# SCH_CarAccessoryKitNoBatteryV1_0.net
KiCad netlist of a schematic drawn in EasyEDA
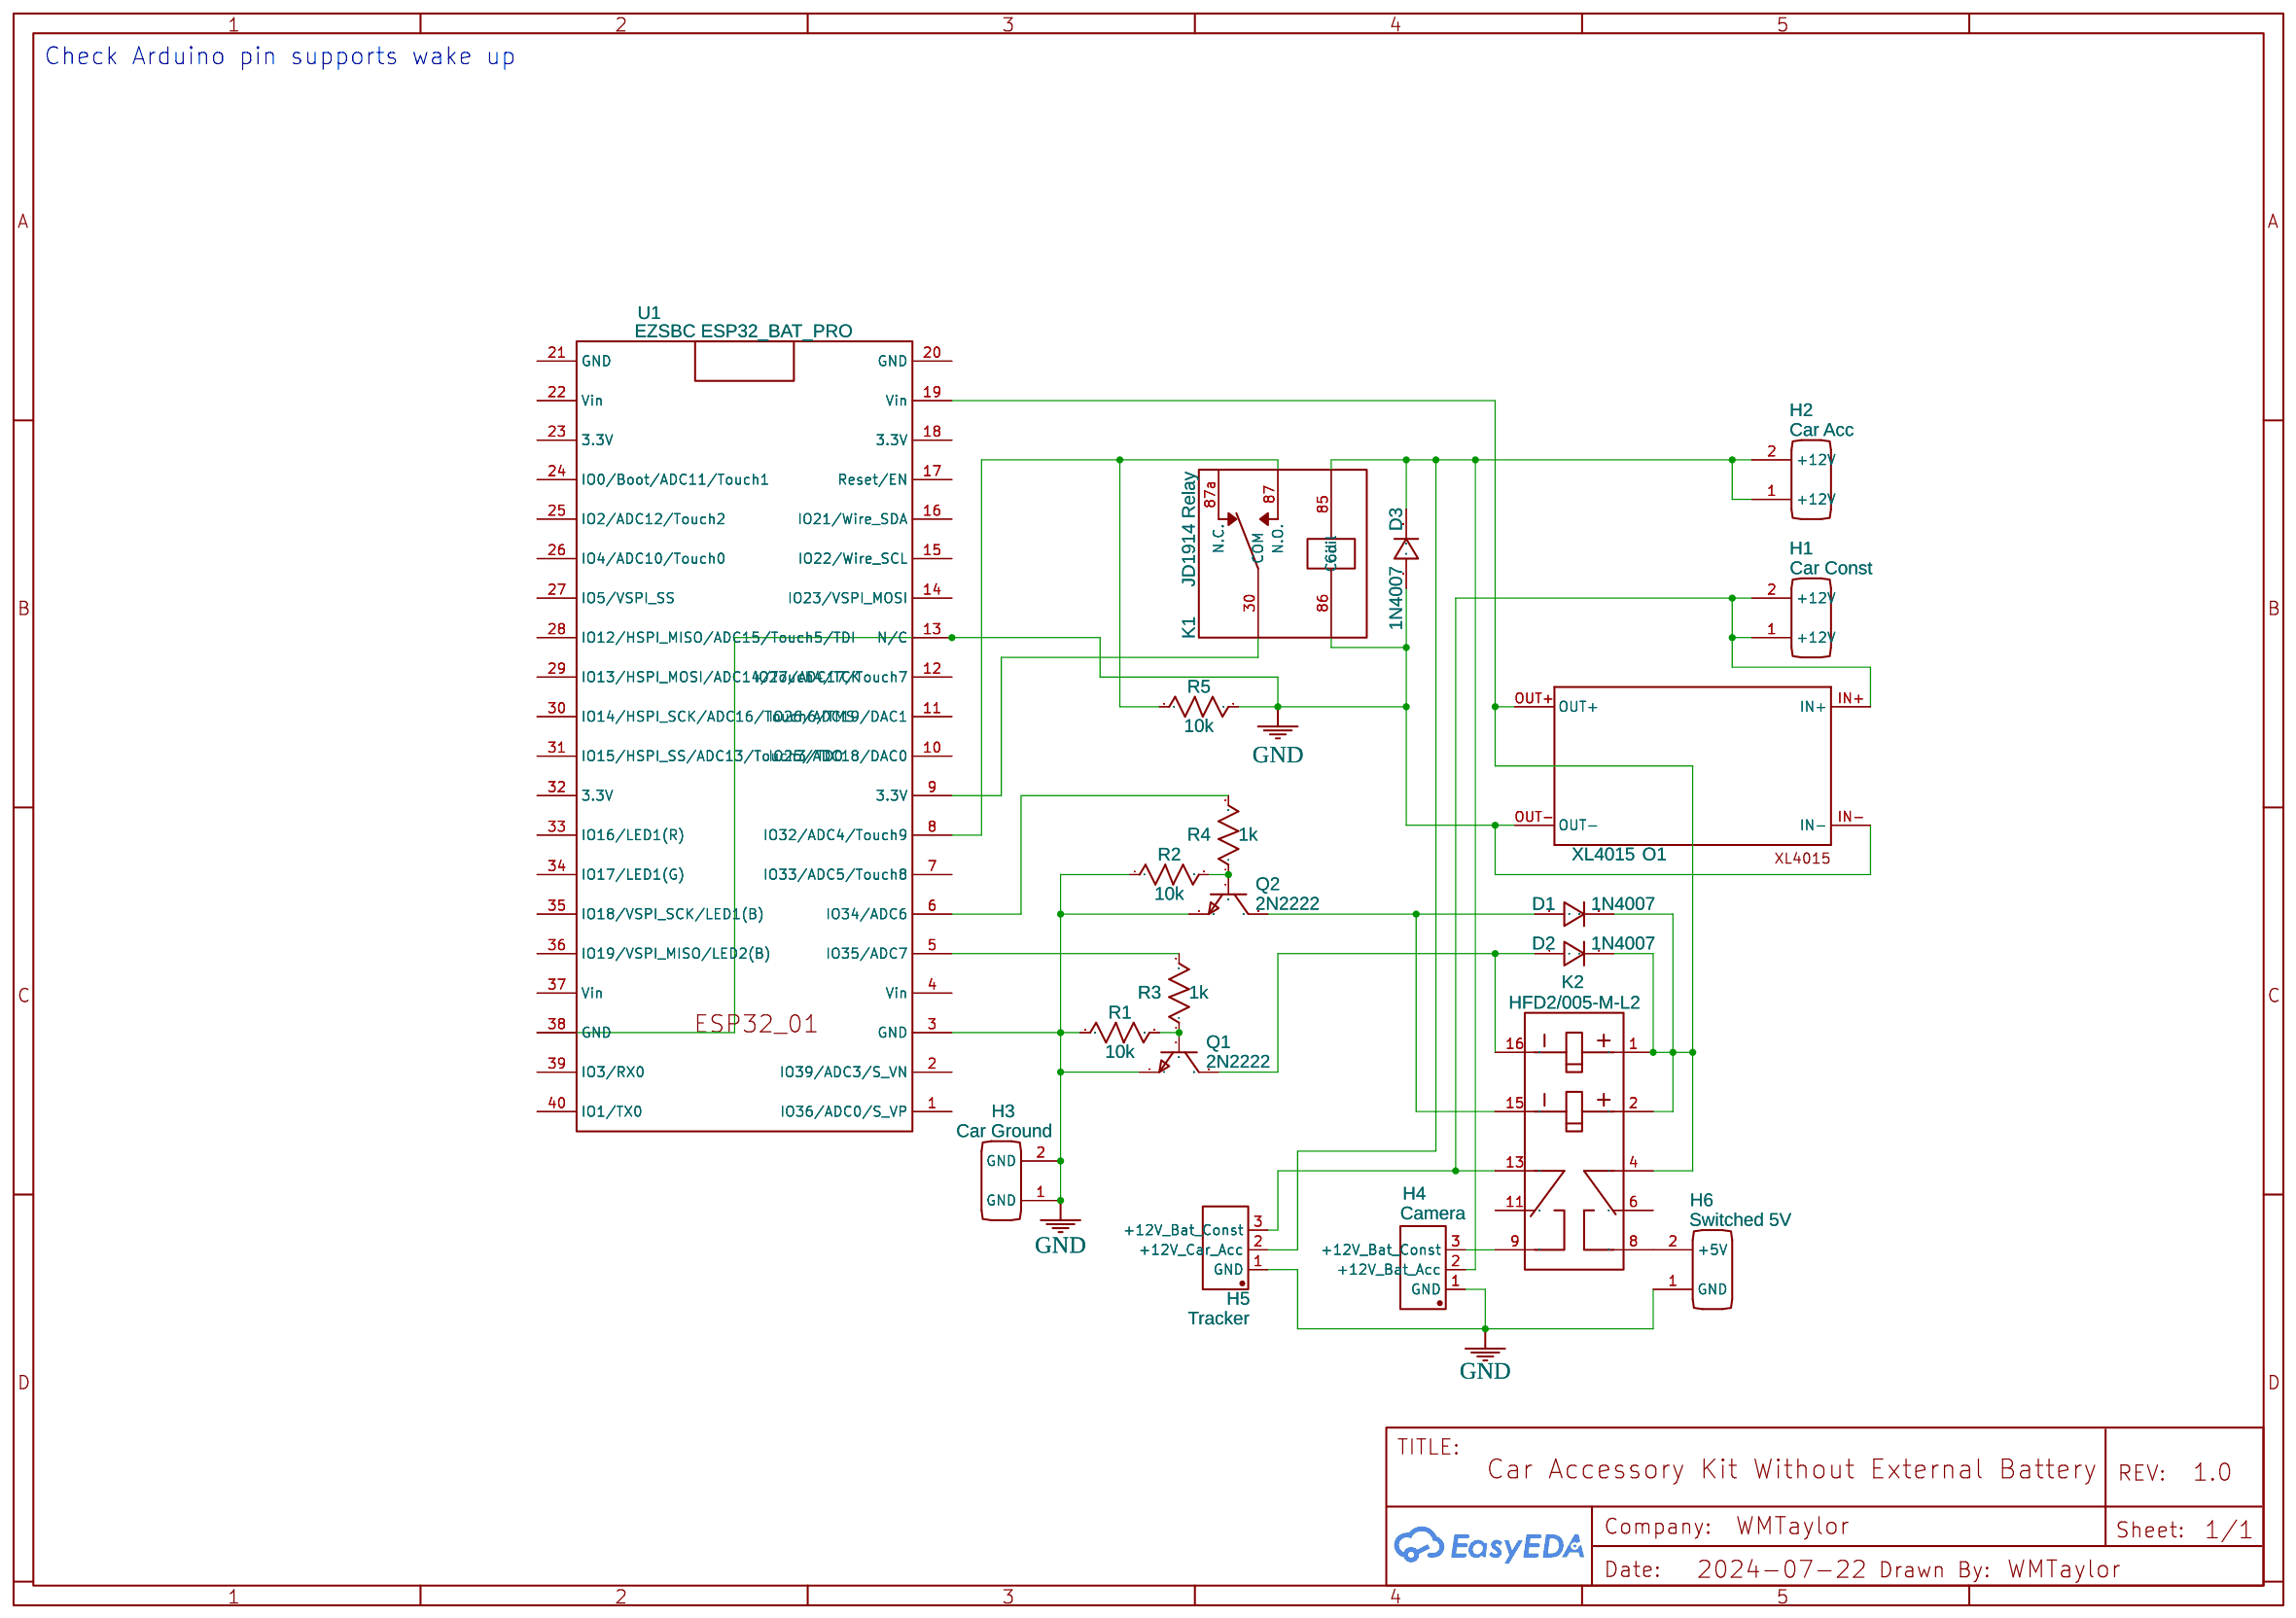
[diagram p0: schematic sheet]

(export (version "E")
  (design (tool "Eeschema 10.0.6"))
  (components
    (comp (ref "D1")
      (value "1N4007")
      (fields (field (name "Manufacturer") "SEMTECH"))
      (libsource (lib "") (part "1N4007_1"))
    )
    (comp (ref "D2")
      (value "1N4007")
      (fields (field (name "Manufacturer") "SEMTECH"))
      (libsource (lib "") (part "1N4007_1"))
    )
    (comp (ref "D3")
      (value "1N4007")
      (fields (field (name "Manufacturer") "SEMTECH"))
      (libsource (lib "") (part "1N4007"))
    )
    (comp (ref "H1") (value "Car Const") (libsource (lib "") (part "JST_VH-2P-3.96")))
    (comp (ref "H2") (value "Car Acc") (libsource (lib "") (part "JST_VH-2P-3.96")))
    (comp (ref "H3") (value "Car Ground") (libsource (lib "") (part "JST_VH-2P-3.96_2")))
    (comp (ref "H4")
      (value "Camera")
      (fields (field (name "Manufacturer Part") "VH-3A") (field (name "Manufacturer") "BOOMELE(博穆精密)"))
      (libsource (lib "") (part "VH3.96-3A_1"))
    )
    (comp (ref "H5")
      (value "Tracker")
      (fields (field (name "Manufacturer Part") "VH-3A") (field (name "Manufacturer") "BOOMELE(博穆精密)"))
      (libsource (lib "") (part "VH3.96-3A"))
    )
    (comp (ref "H6") (value "Switched 5V") (libsource (lib "") (part "JST_VH-2P-3.96_1")))
    (comp (ref "K1")
      (value "JD1914 Relay")
      (fields (field (name "Manufacturer Part") "JD1914") (field (name "Manufacturer") "BenFeng"))
      (libsource (lib "") (part "RELAY JD1914 12V 80A"))
    )
    (comp (ref "K2")
      (value "HFD2/005-M-L2")
      (fields (field (name "Manufacturer") "HF(宏发)"))
      (libsource (lib "") (part "HFD2/005-M-L2"))
    )
    (comp (ref "O1") (value "XL4015") (libsource (lib "") (part "XL4015")))
    (comp (ref "Q1") (value "2N2222") (libsource (lib "") (part "2N2222")))
    (comp (ref "Q2") (value "2N2222") (libsource (lib "") (part "2N2222")))
    (comp (ref "R1") (value "10k") (libsource (lib "") (part "R_AXIAL-0.3_US_1")))
    (comp (ref "R2") (value "10k") (libsource (lib "") (part "R_AXIAL-0.3_US_1")))
    (comp (ref "R3") (value "1k") (libsource (lib "") (part "R_AXIAL-0.3_US")))
    (comp (ref "R4") (value "1k") (libsource (lib "") (part "R_AXIAL-0.3_US")))
    (comp (ref "R5") (value "10k") (libsource (lib "") (part "R_AXIAL-0.3_US_1")))
    (comp (ref "U1")
      (value "EZSBC ESP32_BAT_PRO")
      (fields (field (name "Manufacturer Part") "ESP32_01") (field (name "Manufacturer") "EZSBC"))
      (libsource (lib "") (part "EZSBC ESP32_01"))
    )
  )
  (nets
    (net (code "1") (name "GND") (class "Default")
      (node (ref "D3") (pin "2") (pinfunction "2_2") (pintype "unspecified"))
      (node (ref "H3") (pin "1") (pinfunction "GND_1") (pintype "unspecified"))
      (node (ref "H3") (pin "2") (pinfunction "GND_2") (pintype "unspecified"))
      (node (ref "H4") (pin "1") (pinfunction "GND_1") (pintype "unspecified"))
      (node (ref "H5") (pin "1") (pinfunction "GND_1") (pintype "unspecified"))
      (node (ref "H6") (pin "1") (pinfunction "GND_1") (pintype "unspecified"))
      (node (ref "K1") (pin "86") (pinfunction "Coil_86") (pintype "unspecified"))
      (node (ref "O1") (pin "IN-") (pinfunction "IN-_IN-") (pintype "bidirectional"))
      (node (ref "O1") (pin "OUT-") (pinfunction "OUT-_OUT-") (pintype "bidirectional"))
      (node (ref "Q1") (pin "1") (pinfunction "E_1") (pintype "unspecified"))
      (node (ref "Q2") (pin "1") (pinfunction "E_1") (pintype "unspecified"))
      (node (ref "R1") (pin "1") (pinfunction "1_1") (pintype "unspecified"))
      (node (ref "R2") (pin "1") (pinfunction "1_1") (pintype "unspecified"))
      (node (ref "R5") (pin "2") (pinfunction "2_2") (pintype "unspecified"))
      (node (ref "U1") (pin "13") (pinfunction "N/C_13") (pintype "unspecified"))
      (node (ref "U1") (pin "3") (pinfunction "GND_3") (pintype "unspecified"))
      (node (ref "U1") (pin "38") (pinfunction "GND_38") (pintype "unspecified"))
    )
    (net (code "2") (name "Net-(D1-Pad1)") (class "Default")
      (node (ref "D1") (pin "1") (pinfunction "1_1") (pintype "unspecified"))
      (node (ref "D2") (pin "1") (pinfunction "1_1") (pintype "unspecified"))
      (node (ref "K2") (pin "1") (pinfunction "1_1") (pintype "unspecified"))
      (node (ref "K2") (pin "2") (pinfunction "2_2") (pintype "unspecified"))
      (node (ref "K2") (pin "4") (pinfunction "4_4") (pintype "unspecified"))
      (node (ref "O1") (pin "OUT+") (pinfunction "OUT+_OUT+") (pintype "bidirectional"))
      (node (ref "U1") (pin "19") (pinfunction "Vin_19") (pintype "unspecified"))
    )
    (net (code "3") (name "Net-(H4-+12V_Bat_Acc)") (class "Default")
      (node (ref "D3") (pin "1") (pinfunction "1_1") (pintype "unspecified"))
      (node (ref "H2") (pin "1") (pinfunction "+12V_1") (pintype "unspecified"))
      (node (ref "H2") (pin "2") (pinfunction "+12V_2") (pintype "unspecified"))
      (node (ref "H4") (pin "2") (pinfunction "+12V_Bat_Acc_2") (pintype "unspecified"))
      (node (ref "H5") (pin "2") (pinfunction "+12V_Car_Acc_2") (pintype "unspecified"))
      (node (ref "K1") (pin "85") (pinfunction "Coil_85") (pintype "unspecified"))
    )
    (net (code "4") (name "Net-(H4-+12V_Bat_Const)") (class "Default")
      (node (ref "H4") (pin "3") (pinfunction "+12V_Bat_Const_3") (pintype "unspecified"))
      (node (ref "K2") (pin "9") (pinfunction "9_9") (pintype "unspecified"))
    )
    (net (code "5") (name "Net-(H5-+12V_Bat_Const)") (class "Default")
      (node (ref "H1") (pin "1") (pinfunction "+12V_1") (pintype "unspecified"))
      (node (ref "H1") (pin "2") (pinfunction "+12V_2") (pintype "unspecified"))
      (node (ref "H5") (pin "3") (pinfunction "+12V_Bat_Const_3") (pintype "unspecified"))
      (node (ref "K2") (pin "13") (pinfunction "13_13") (pintype "unspecified"))
      (node (ref "O1") (pin "IN+") (pinfunction "IN+_IN+") (pintype "bidirectional"))
    )
    (net (code "6") (name "Net-(H6-+5V)") (class "Default")
      (node (ref "H6") (pin "2") (pinfunction "+5V_2") (pintype "unspecified"))
      (node (ref "K2") (pin "8") (pinfunction "8_8") (pintype "unspecified"))
    )
    (net (code "7") (name "Net-(K1-COM)") (class "Default")
      (node (ref "K1") (pin "30") (pinfunction "COM_30") (pintype "unspecified"))
      (node (ref "U1") (pin "9") (pinfunction "3.3V_9") (pintype "unspecified"))
    )
    (net (code "8") (name "Net-(K1-N.O.)") (class "Default")
      (node (ref "K1") (pin "87") (pinfunction "N.O._87") (pintype "unspecified"))
      (node (ref "R5") (pin "1") (pinfunction "1_1") (pintype "unspecified"))
      (node (ref "U1") (pin "8") (pinfunction "IO32/ADC4/Touch9_8") (pintype "unspecified"))
    )
    (net (code "9") (name "Net-(Q1-B)") (class "Default")
      (node (ref "Q1") (pin "2") (pinfunction "B_2") (pintype "unspecified"))
      (node (ref "R1") (pin "2") (pinfunction "2_2") (pintype "unspecified"))
      (node (ref "R3") (pin "1") (pinfunction "1_1") (pintype "unspecified"))
    )
    (net (code "10") (name "Net-(Q1-C)") (class "Default")
      (node (ref "D2") (pin "2") (pinfunction "2_2") (pintype "unspecified"))
      (node (ref "K2") (pin "16") (pinfunction "16_16") (pintype "unspecified"))
      (node (ref "Q1") (pin "3") (pinfunction "C_3") (pintype "unspecified"))
    )
    (net (code "11") (name "Net-(Q2-B)") (class "Default")
      (node (ref "Q2") (pin "2") (pinfunction "B_2") (pintype "unspecified"))
      (node (ref "R2") (pin "2") (pinfunction "2_2") (pintype "unspecified"))
      (node (ref "R4") (pin "1") (pinfunction "1_1") (pintype "unspecified"))
    )
    (net (code "12") (name "Net-(Q2-C)") (class "Default")
      (node (ref "D1") (pin "2") (pinfunction "2_2") (pintype "unspecified"))
      (node (ref "K2") (pin "15") (pinfunction "15_15") (pintype "unspecified"))
      (node (ref "Q2") (pin "3") (pinfunction "C_3") (pintype "unspecified"))
    )
    (net (code "13") (name "Net-(U1-IO34{slash}ADC6)") (class "Default")
      (node (ref "R4") (pin "2") (pinfunction "2_2") (pintype "unspecified"))
      (node (ref "U1") (pin "6") (pinfunction "IO34/ADC6_6") (pintype "unspecified"))
    )
    (net (code "14") (name "Net-(U1-IO35{slash}ADC7)") (class "Default")
      (node (ref "R3") (pin "2") (pinfunction "2_2") (pintype "unspecified"))
      (node (ref "U1") (pin "5") (pinfunction "IO35/ADC7_5") (pintype "unspecified"))
    )
    (net (code "15") (name "unconnected-(K1-N.C.-Pad87a)") (class "Default")
      (node (ref "K1") (pin "87a") (pinfunction "N.C._87a") (pintype "unspecified"))
    )
    (net (code "16") (name "unconnected-(K2-Pad6)") (class "Default")
      (node (ref "K2") (pin "6") (pinfunction "6_6") (pintype "unspecified"))
    )
    (net (code "17") (name "unconnected-(K2-Pad11)") (class "Default")
      (node (ref "K2") (pin "11") (pinfunction "11_11") (pintype "unspecified"))
    )
    (net (code "18") (name "unconnected-(U1-3.3V-Pad18)") (class "Default")
      (node (ref "U1") (pin "18") (pinfunction "3.3V_18") (pintype "unspecified"))
    )
    (net (code "19") (name "unconnected-(U1-3.3V-Pad23)") (class "Default")
      (node (ref "U1") (pin "23") (pinfunction "3.3V_23") (pintype "unspecified"))
    )
    (net (code "20") (name "unconnected-(U1-3.3V-Pad32)") (class "Default")
      (node (ref "U1") (pin "32") (pinfunction "3.3V_32") (pintype "unspecified"))
    )
    (net (code "21") (name "unconnected-(U1-GND-Pad20)") (class "Default")
      (node (ref "U1") (pin "20") (pinfunction "GND_20") (pintype "unspecified"))
    )
    (net (code "22") (name "unconnected-(U1-GND-Pad21)") (class "Default")
      (node (ref "U1") (pin "21") (pinfunction "GND_21") (pintype "unspecified"))
    )
    (net (code "23") (name "unconnected-(U1-IO0{slash}Boot{slash}ADC11{slash}Touch1-Pad24)") (class "Default")
      (node (ref "U1") (pin "24") (pinfunction "IO0/Boot/ADC11/Touch1_24") (pintype "unspecified"))
    )
    (net (code "24") (name "unconnected-(U1-IO1{slash}TX0-Pad40)") (class "Default")
      (node (ref "U1") (pin "40") (pinfunction "IO1/TX0_40") (pintype "unspecified"))
    )
    (net (code "25") (name "unconnected-(U1-IO2{slash}ADC12{slash}Touch2-Pad25)") (class "Default")
      (node (ref "U1") (pin "25") (pinfunction "IO2/ADC12/Touch2_25") (pintype "unspecified"))
    )
    (net (code "26") (name "unconnected-(U1-IO3{slash}RX0-Pad39)") (class "Default")
      (node (ref "U1") (pin "39") (pinfunction "IO3/RX0_39") (pintype "unspecified"))
    )
    (net (code "27") (name "unconnected-(U1-IO4{slash}ADC10{slash}Touch0-Pad26)") (class "Default")
      (node (ref "U1") (pin "26") (pinfunction "IO4/ADC10/Touch0_26") (pintype "unspecified"))
    )
    (net (code "28") (name "unconnected-(U1-IO5{slash}VSPI_SS-Pad27)") (class "Default")
      (node (ref "U1") (pin "27") (pinfunction "IO5/VSPI_SS_27") (pintype "unspecified"))
    )
    (net (code "29") (name "unconnected-(U1-IO12{slash}HSPI_MISO{slash}ADC15{slash}Touch5{slash}TDI-Pad28)") (class "Default")
      (node (ref "U1") (pin "28") (pinfunction "IO12/HSPI_MISO/ADC15/Touch5/TDI_28") (pintype "unspecified"))
    )
    (net (code "30") (name "unconnected-(U1-IO13{slash}HSPI_MOSI{slash}ADC14{slash}Touch4{slash}TCK-Pad29)") (class "Default")
      (node (ref "U1") (pin "29") (pinfunction "IO13/HSPI_MOSI/ADC14/Touch4/TCK_29") (pintype "unspecified"))
    )
    (net (code "31") (name "unconnected-(U1-IO14{slash}HSPI_SCK{slash}ADC16{slash}Touch6{slash}TMS-Pad30)") (class "Default")
      (node (ref "U1") (pin "30") (pinfunction "IO14/HSPI_SCK/ADC16/Touch6/TMS_30") (pintype "unspecified"))
    )
    (net (code "32") (name "unconnected-(U1-IO15{slash}HSPI_SS{slash}ADC13{slash}Touch3{slash}TD0-Pad31)") (class "Default")
      (node (ref "U1") (pin "31") (pinfunction "IO15/HSPI_SS/ADC13/Touch3/TD0_31") (pintype "unspecified"))
    )
    (net (code "33") (name "unconnected-(U1-IO16{slash}LED1(R)-Pad33)") (class "Default")
      (node (ref "U1") (pin "33") (pinfunction "IO16/LED1(R)_33") (pintype "unspecified"))
    )
    (net (code "34") (name "unconnected-(U1-IO17{slash}LED1(G)-Pad34)") (class "Default")
      (node (ref "U1") (pin "34") (pinfunction "IO17/LED1(G)_34") (pintype "unspecified"))
    )
    (net (code "35") (name "unconnected-(U1-IO18{slash}VSPI_SCK{slash}LED1(B)-Pad35)") (class "Default")
      (node (ref "U1") (pin "35") (pinfunction "IO18/VSPI_SCK/LED1(B)_35") (pintype "unspecified"))
    )
    (net (code "36") (name "unconnected-(U1-IO19{slash}VSPI_MISO{slash}LED2(B)-Pad36)") (class "Default")
      (node (ref "U1") (pin "36") (pinfunction "IO19/VSPI_MISO/LED2(B)_36") (pintype "unspecified"))
    )
    (net (code "37") (name "unconnected-(U1-IO21{slash}Wire_SDA-Pad16)") (class "Default")
      (node (ref "U1") (pin "16") (pinfunction "IO21/Wire_SDA_16") (pintype "unspecified"))
    )
    (net (code "38") (name "unconnected-(U1-IO22{slash}Wire_SCL-Pad15)") (class "Default")
      (node (ref "U1") (pin "15") (pinfunction "IO22/Wire_SCL_15") (pintype "unspecified"))
    )
    (net (code "39") (name "unconnected-(U1-IO23{slash}VSPI_MOSI-Pad14)") (class "Default")
      (node (ref "U1") (pin "14") (pinfunction "IO23/VSPI_MOSI_14") (pintype "unspecified"))
    )
    (net (code "40") (name "unconnected-(U1-IO25{slash}ADC18{slash}DAC0-Pad10)") (class "Default")
      (node (ref "U1") (pin "10") (pinfunction "IO25/ADC18/DAC0_10") (pintype "unspecified"))
    )
    (net (code "41") (name "unconnected-(U1-IO26{slash}ADC19{slash}DAC1-Pad11)") (class "Default")
      (node (ref "U1") (pin "11") (pinfunction "IO26/ADC19/DAC1_11") (pintype "unspecified"))
    )
    (net (code "42") (name "unconnected-(U1-IO27{slash}ADC17{slash}Touch7-Pad12)") (class "Default")
      (node (ref "U1") (pin "12") (pinfunction "IO27/ADC17/Touch7_12") (pintype "unspecified"))
    )
    (net (code "43") (name "unconnected-(U1-IO33{slash}ADC5{slash}Touch8-Pad7)") (class "Default")
      (node (ref "U1") (pin "7") (pinfunction "IO33/ADC5/Touch8_7") (pintype "unspecified"))
    )
    (net (code "44") (name "unconnected-(U1-IO36{slash}ADC0{slash}S_VP-Pad1)") (class "Default")
      (node (ref "U1") (pin "1") (pinfunction "IO36/ADC0/S_VP_1") (pintype "unspecified"))
    )
    (net (code "45") (name "unconnected-(U1-IO39{slash}ADC3{slash}S_VN-Pad2)") (class "Default")
      (node (ref "U1") (pin "2") (pinfunction "IO39/ADC3/S_VN_2") (pintype "unspecified"))
    )
    (net (code "46") (name "unconnected-(U1-Reset{slash}EN-Pad17)") (class "Default")
      (node (ref "U1") (pin "17") (pinfunction "Reset/EN_17") (pintype "unspecified"))
    )
    (net (code "47") (name "unconnected-(U1-Vin-Pad4)") (class "Default")
      (node (ref "U1") (pin "4") (pinfunction "Vin_4") (pintype "unspecified"))
    )
    (net (code "48") (name "unconnected-(U1-Vin-Pad22)") (class "Default")
      (node (ref "U1") (pin "22") (pinfunction "Vin_22") (pintype "unspecified"))
    )
    (net (code "49") (name "unconnected-(U1-Vin-Pad37)") (class "Default")
      (node (ref "U1") (pin "37") (pinfunction "Vin_37") (pintype "unspecified"))
    )
  )
)
